# Board.net
KiCad netlist of a schematic drawn in EAGLE
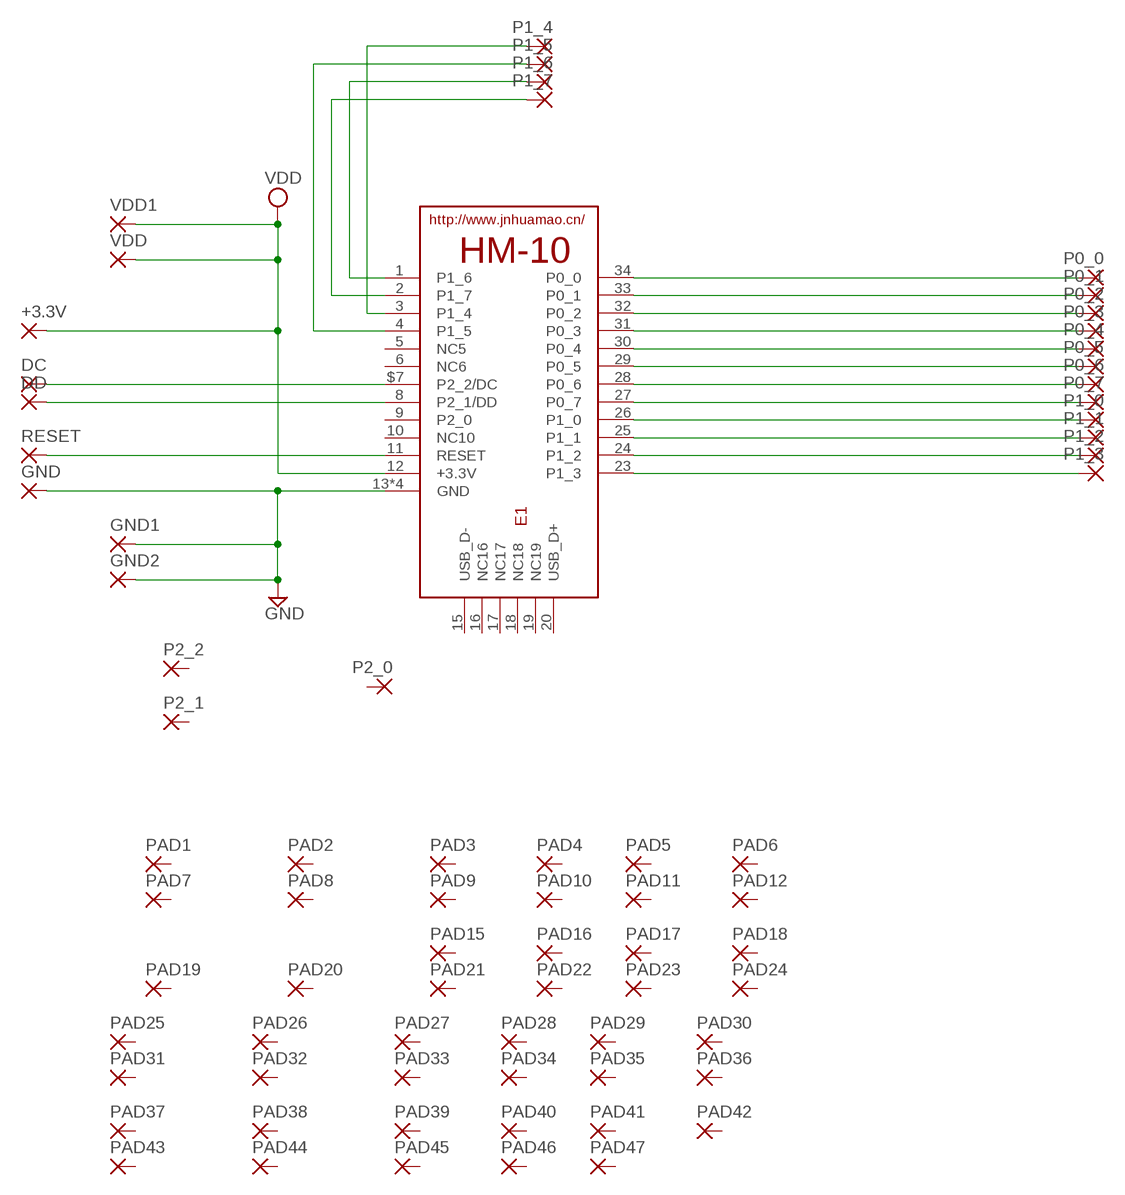
[diagram p0: schematic, sheet 1]

(export (version "E")
  (design (tool "Eeschema 10.0.6"))
  (components
    (comp (ref "+3.3V")
      (value "SMD2")
      (footprint "eagle-import:SMD1,27-2,54")
      (libsource (lib "eagle-import") (part "SMD2"))
    )
    (comp (ref "DC")
      (value "SMD2")
      (footprint "eagle-import:SMD1,27-2,54")
      (libsource (lib "eagle-import") (part "SMD2"))
    )
    (comp (ref "DD")
      (value "SMD2")
      (footprint "eagle-import:SMD1,27-2,54")
      (libsource (lib "eagle-import") (part "SMD2"))
    )
    (comp (ref "E1")
      (value "HM-10-BOARD")
      (footprint "eagle-import:26.9X13X2.2_BOARD")
      (libsource (lib "eagle-import") (part "HM-10-BOARD"))
    )
    (comp (ref "GND")
      (value "SMD2")
      (footprint "eagle-import:SMD1,27-2,54")
      (libsource (lib "eagle-import") (part "SMD2"))
    )
    (comp (ref "GND1")
      (value "1,6/0,9")
      (footprint "eagle-import:1,6_0,9")
      (libsource (lib "eagle-import") (part "1,6/0,9"))
    )
    (comp (ref "GND2")
      (value "1,6/0,9")
      (footprint "eagle-import:1,6_0,9")
      (libsource (lib "eagle-import") (part "1,6/0,9"))
    )
    (comp (ref "P0_0")
      (value "1,6/0,9")
      (footprint "eagle-import:1,6_0,9")
      (libsource (lib "eagle-import") (part "1,6/0,9"))
    )
    (comp (ref "P0_1")
      (value "1,6/0,9")
      (footprint "eagle-import:1,6_0,9")
      (libsource (lib "eagle-import") (part "1,6/0,9"))
    )
    (comp (ref "P0_2")
      (value "1,6/0,9")
      (footprint "eagle-import:1,6_0,9")
      (libsource (lib "eagle-import") (part "1,6/0,9"))
    )
    (comp (ref "P0_3")
      (value "1,6/0,9")
      (footprint "eagle-import:1,6_0,9")
      (libsource (lib "eagle-import") (part "1,6/0,9"))
    )
    (comp (ref "P0_4")
      (value "1,6/0,9")
      (footprint "eagle-import:1,6_0,9")
      (libsource (lib "eagle-import") (part "1,6/0,9"))
    )
    (comp (ref "P0_5")
      (value "1,6/0,9")
      (footprint "eagle-import:1,6_0,9")
      (libsource (lib "eagle-import") (part "1,6/0,9"))
    )
    (comp (ref "P0_6")
      (value "1,6/0,9")
      (footprint "eagle-import:1,6_0,9")
      (libsource (lib "eagle-import") (part "1,6/0,9"))
    )
    (comp (ref "P0_7")
      (value "1,6/0,9")
      (footprint "eagle-import:1,6_0,9")
      (libsource (lib "eagle-import") (part "1,6/0,9"))
    )
    (comp (ref "P1_0")
      (value "1,6/0,9")
      (footprint "eagle-import:1,6_0,9")
      (libsource (lib "eagle-import") (part "1,6/0,9"))
    )
    (comp (ref "P1_1")
      (value "1,6/0,9")
      (footprint "eagle-import:1,6_0,9")
      (libsource (lib "eagle-import") (part "1,6/0,9"))
    )
    (comp (ref "P1_2")
      (value "1,6/0,9")
      (footprint "eagle-import:1,6_0,9")
      (libsource (lib "eagle-import") (part "1,6/0,9"))
    )
    (comp (ref "P1_3")
      (value "1,6/0,9")
      (footprint "eagle-import:1,6_0,9")
      (libsource (lib "eagle-import") (part "1,6/0,9"))
    )
    (comp (ref "P1_4")
      (value "1,6/0,9")
      (footprint "eagle-import:1,6_0,9")
      (libsource (lib "eagle-import") (part "1,6/0,9"))
    )
    (comp (ref "P1_5")
      (value "1,6/0,9")
      (footprint "eagle-import:1,6_0,9")
      (libsource (lib "eagle-import") (part "1,6/0,9"))
    )
    (comp (ref "P1_6")
      (value "1,6/0,9")
      (footprint "eagle-import:1,6_0,9")
      (libsource (lib "eagle-import") (part "1,6/0,9"))
    )
    (comp (ref "P1_7")
      (value "1,6/0,9")
      (footprint "eagle-import:1,6_0,9")
      (libsource (lib "eagle-import") (part "1,6/0,9"))
    )
    (comp (ref "P2_0")
      (value "1,6/0,9")
      (footprint "eagle-import:1,6_0,9")
      (libsource (lib "eagle-import") (part "1,6/0,9"))
    )
    (comp (ref "P2_1")
      (value "1,6/0,9")
      (footprint "eagle-import:1,6_0,9")
      (libsource (lib "eagle-import") (part "1,6/0,9"))
    )
    (comp (ref "P2_2")
      (value "1,6/0,9")
      (footprint "eagle-import:1,6_0,9")
      (libsource (lib "eagle-import") (part "1,6/0,9"))
    )
    (comp (ref "PAD1")
      (value "1,6/0,9")
      (footprint "eagle-import:1,6_0,9")
      (libsource (lib "eagle-import") (part "1,6/0,9"))
    )
    (comp (ref "PAD2")
      (value "1,6/0,9")
      (footprint "eagle-import:1,6_0,9")
      (libsource (lib "eagle-import") (part "1,6/0,9"))
    )
    (comp (ref "PAD3")
      (value "1,6/0,9")
      (footprint "eagle-import:1,6_0,9")
      (libsource (lib "eagle-import") (part "1,6/0,9"))
    )
    (comp (ref "PAD4")
      (value "1,6/0,9")
      (footprint "eagle-import:1,6_0,9")
      (libsource (lib "eagle-import") (part "1,6/0,9"))
    )
    (comp (ref "PAD5")
      (value "1,6/0,9")
      (footprint "eagle-import:1,6_0,9")
      (libsource (lib "eagle-import") (part "1,6/0,9"))
    )
    (comp (ref "PAD6")
      (value "1,6/0,9")
      (footprint "eagle-import:1,6_0,9")
      (libsource (lib "eagle-import") (part "1,6/0,9"))
    )
    (comp (ref "PAD7")
      (value "1,6/0,9")
      (footprint "eagle-import:1,6_0,9")
      (libsource (lib "eagle-import") (part "1,6/0,9"))
    )
    (comp (ref "PAD8")
      (value "1,6/0,9")
      (footprint "eagle-import:1,6_0,9")
      (libsource (lib "eagle-import") (part "1,6/0,9"))
    )
    (comp (ref "PAD9")
      (value "1,6/0,9")
      (footprint "eagle-import:1,6_0,9")
      (libsource (lib "eagle-import") (part "1,6/0,9"))
    )
    (comp (ref "PAD10")
      (value "1,6/0,9")
      (footprint "eagle-import:1,6_0,9")
      (libsource (lib "eagle-import") (part "1,6/0,9"))
    )
    (comp (ref "PAD11")
      (value "1,6/0,9")
      (footprint "eagle-import:1,6_0,9")
      (libsource (lib "eagle-import") (part "1,6/0,9"))
    )
    (comp (ref "PAD12")
      (value "1,6/0,9")
      (footprint "eagle-import:1,6_0,9")
      (libsource (lib "eagle-import") (part "1,6/0,9"))
    )
    (comp (ref "PAD15")
      (value "1,6/0,9")
      (footprint "eagle-import:1,6_0,9")
      (libsource (lib "eagle-import") (part "1,6/0,9"))
    )
    (comp (ref "PAD16")
      (value "1,6/0,9")
      (footprint "eagle-import:1,6_0,9")
      (libsource (lib "eagle-import") (part "1,6/0,9"))
    )
    (comp (ref "PAD17")
      (value "1,6/0,9")
      (footprint "eagle-import:1,6_0,9")
      (libsource (lib "eagle-import") (part "1,6/0,9"))
    )
    (comp (ref "PAD18")
      (value "1,6/0,9")
      (footprint "eagle-import:1,6_0,9")
      (libsource (lib "eagle-import") (part "1,6/0,9"))
    )
    (comp (ref "PAD19")
      (value "1,6/0,9")
      (footprint "eagle-import:1,6_0,9")
      (libsource (lib "eagle-import") (part "1,6/0,9"))
    )
    (comp (ref "PAD20")
      (value "1,6/0,9")
      (footprint "eagle-import:1,6_0,9")
      (libsource (lib "eagle-import") (part "1,6/0,9"))
    )
    (comp (ref "PAD21")
      (value "1,6/0,9")
      (footprint "eagle-import:1,6_0,9")
      (libsource (lib "eagle-import") (part "1,6/0,9"))
    )
    (comp (ref "PAD22")
      (value "1,6/0,9")
      (footprint "eagle-import:1,6_0,9")
      (libsource (lib "eagle-import") (part "1,6/0,9"))
    )
    (comp (ref "PAD23")
      (value "1,6/0,9")
      (footprint "eagle-import:1,6_0,9")
      (libsource (lib "eagle-import") (part "1,6/0,9"))
    )
    (comp (ref "PAD24")
      (value "1,6/0,9")
      (footprint "eagle-import:1,6_0,9")
      (libsource (lib "eagle-import") (part "1,6/0,9"))
    )
    (comp (ref "PAD25")
      (value "1,6/0,9")
      (footprint "eagle-import:1,6_0,9")
      (libsource (lib "eagle-import") (part "1,6/0,9"))
    )
    (comp (ref "PAD26")
      (value "1,6/0,9")
      (footprint "eagle-import:1,6_0,9")
      (libsource (lib "eagle-import") (part "1,6/0,9"))
    )
    (comp (ref "PAD27")
      (value "1,6/0,9")
      (footprint "eagle-import:1,6_0,9")
      (libsource (lib "eagle-import") (part "1,6/0,9"))
    )
    (comp (ref "PAD28")
      (value "1,6/0,9")
      (footprint "eagle-import:1,6_0,9")
      (libsource (lib "eagle-import") (part "1,6/0,9"))
    )
    (comp (ref "PAD29")
      (value "1,6/0,9")
      (footprint "eagle-import:1,6_0,9")
      (libsource (lib "eagle-import") (part "1,6/0,9"))
    )
    (comp (ref "PAD30")
      (value "1,6/0,9")
      (footprint "eagle-import:1,6_0,9")
      (libsource (lib "eagle-import") (part "1,6/0,9"))
    )
    (comp (ref "PAD31")
      (value "1,6/0,9")
      (footprint "eagle-import:1,6_0,9")
      (libsource (lib "eagle-import") (part "1,6/0,9"))
    )
    (comp (ref "PAD32")
      (value "1,6/0,9")
      (footprint "eagle-import:1,6_0,9")
      (libsource (lib "eagle-import") (part "1,6/0,9"))
    )
    (comp (ref "PAD33")
      (value "1,6/0,9")
      (footprint "eagle-import:1,6_0,9")
      (libsource (lib "eagle-import") (part "1,6/0,9"))
    )
    (comp (ref "PAD34")
      (value "1,6/0,9")
      (footprint "eagle-import:1,6_0,9")
      (libsource (lib "eagle-import") (part "1,6/0,9"))
    )
    (comp (ref "PAD35")
      (value "1,6/0,9")
      (footprint "eagle-import:1,6_0,9")
      (libsource (lib "eagle-import") (part "1,6/0,9"))
    )
    (comp (ref "PAD36")
      (value "1,6/0,9")
      (footprint "eagle-import:1,6_0,9")
      (libsource (lib "eagle-import") (part "1,6/0,9"))
    )
    (comp (ref "PAD37")
      (value "1,6/0,9")
      (footprint "eagle-import:1,6_0,9")
      (libsource (lib "eagle-import") (part "1,6/0,9"))
    )
    (comp (ref "PAD38")
      (value "1,6/0,9")
      (footprint "eagle-import:1,6_0,9")
      (libsource (lib "eagle-import") (part "1,6/0,9"))
    )
    (comp (ref "PAD39")
      (value "1,6/0,9")
      (footprint "eagle-import:1,6_0,9")
      (libsource (lib "eagle-import") (part "1,6/0,9"))
    )
    (comp (ref "PAD40")
      (value "1,6/0,9")
      (footprint "eagle-import:1,6_0,9")
      (libsource (lib "eagle-import") (part "1,6/0,9"))
    )
    (comp (ref "PAD41")
      (value "1,6/0,9")
      (footprint "eagle-import:1,6_0,9")
      (libsource (lib "eagle-import") (part "1,6/0,9"))
    )
    (comp (ref "PAD42")
      (value "1,6/0,9")
      (footprint "eagle-import:1,6_0,9")
      (libsource (lib "eagle-import") (part "1,6/0,9"))
    )
    (comp (ref "PAD43")
      (value "1,6/0,9")
      (footprint "eagle-import:1,6_0,9")
      (libsource (lib "eagle-import") (part "1,6/0,9"))
    )
    (comp (ref "PAD44")
      (value "1,6/0,9")
      (footprint "eagle-import:1,6_0,9")
      (libsource (lib "eagle-import") (part "1,6/0,9"))
    )
    (comp (ref "PAD45")
      (value "1,6/0,9")
      (footprint "eagle-import:1,6_0,9")
      (libsource (lib "eagle-import") (part "1,6/0,9"))
    )
    (comp (ref "PAD46")
      (value "1,6/0,9")
      (footprint "eagle-import:1,6_0,9")
      (libsource (lib "eagle-import") (part "1,6/0,9"))
    )
    (comp (ref "PAD47")
      (value "1,6/0,9")
      (footprint "eagle-import:1,6_0,9")
      (libsource (lib "eagle-import") (part "1,6/0,9"))
    )
    (comp (ref "RESET")
      (value "SMD2")
      (footprint "eagle-import:SMD1,27-2,54")
      (libsource (lib "eagle-import") (part "SMD2"))
    )
    (comp (ref "VDD")
      (value "1,6/0,9")
      (footprint "eagle-import:1,6_0,9")
      (libsource (lib "eagle-import") (part "1,6/0,9"))
    )
    (comp (ref "VDD1")
      (value "1,6/0,9")
      (footprint "eagle-import:1,6_0,9")
      (libsource (lib "eagle-import") (part "1,6/0,9"))
    )
  )
  (nets
    (net (code "1") (name "GND") (class "Default")
      (node (ref "E1") (pin "13") (pinfunction "GND_13") (pintype "bidirectional"))
      (node (ref "E1") (pin "14") (pinfunction "GND_14") (pintype "bidirectional"))
      (node (ref "E1") (pin "21") (pinfunction "GND_21") (pintype "bidirectional"))
      (node (ref "E1") (pin "22") (pinfunction "GND_22") (pintype "bidirectional"))
      (node (ref "GND") (pin "1") (pinfunction "P_1") (pintype "passive"))
      (node (ref "GND1") (pin "1") (pinfunction "P_1") (pintype "passive"))
      (node (ref "GND2") (pin "1") (pinfunction "P_1") (pintype "passive"))
    )
    (net (code "2") (name "Net-(DC-P)") (class "Default")
      (node (ref "DC") (pin "1") (pinfunction "P_1") (pintype "passive"))
      (node (ref "E1") (pin "$7") (pinfunction "P2_2/DC_$7") (pintype "bidirectional"))
    )
    (net (code "3") (name "Net-(DD-P)") (class "Default")
      (node (ref "DD") (pin "1") (pinfunction "P_1") (pintype "passive"))
      (node (ref "E1") (pin "8") (pinfunction "P2_1/DD_8") (pintype "bidirectional"))
    )
    (net (code "4") (name "Net-(E1-P0_0)") (class "Default")
      (node (ref "E1") (pin "34") (pinfunction "P0_0_34") (pintype "bidirectional"))
      (node (ref "P0_0") (pin "1") (pinfunction "P_1") (pintype "passive"))
    )
    (net (code "5") (name "Net-(E1-P0_1)") (class "Default")
      (node (ref "E1") (pin "33") (pinfunction "P0_1_33") (pintype "bidirectional"))
      (node (ref "P0_1") (pin "1") (pinfunction "P_1") (pintype "passive"))
    )
    (net (code "6") (name "Net-(E1-P0_2)") (class "Default")
      (node (ref "E1") (pin "32") (pinfunction "P0_2_32") (pintype "bidirectional"))
      (node (ref "P0_2") (pin "1") (pinfunction "P_1") (pintype "passive"))
    )
    (net (code "7") (name "Net-(E1-P0_3)") (class "Default")
      (node (ref "E1") (pin "31") (pinfunction "P0_3_31") (pintype "bidirectional"))
      (node (ref "P0_3") (pin "1") (pinfunction "P_1") (pintype "passive"))
    )
    (net (code "8") (name "Net-(E1-P0_4)") (class "Default")
      (node (ref "E1") (pin "30") (pinfunction "P0_4_30") (pintype "bidirectional"))
      (node (ref "P0_4") (pin "1") (pinfunction "P_1") (pintype "passive"))
    )
    (net (code "9") (name "Net-(E1-P0_5)") (class "Default")
      (node (ref "E1") (pin "29") (pinfunction "P0_5_29") (pintype "bidirectional"))
      (node (ref "P0_5") (pin "1") (pinfunction "P_1") (pintype "passive"))
    )
    (net (code "10") (name "Net-(E1-P0_6)") (class "Default")
      (node (ref "E1") (pin "28") (pinfunction "P0_6_28") (pintype "bidirectional"))
      (node (ref "P0_6") (pin "1") (pinfunction "P_1") (pintype "passive"))
    )
    (net (code "11") (name "Net-(E1-P0_7)") (class "Default")
      (node (ref "E1") (pin "27") (pinfunction "P0_7_27") (pintype "bidirectional"))
      (node (ref "P0_7") (pin "1") (pinfunction "P_1") (pintype "passive"))
    )
    (net (code "12") (name "Net-(E1-P1_0)") (class "Default")
      (node (ref "E1") (pin "26") (pinfunction "P1_0_26") (pintype "bidirectional"))
      (node (ref "P1_0") (pin "1") (pinfunction "P_1") (pintype "passive"))
    )
    (net (code "13") (name "Net-(E1-P1_1)") (class "Default")
      (node (ref "E1") (pin "25") (pinfunction "P1_1_25") (pintype "bidirectional"))
      (node (ref "P1_1") (pin "1") (pinfunction "P_1") (pintype "passive"))
    )
    (net (code "14") (name "Net-(E1-P1_2)") (class "Default")
      (node (ref "E1") (pin "24") (pinfunction "P1_2_24") (pintype "bidirectional"))
      (node (ref "P1_2") (pin "1") (pinfunction "P_1") (pintype "passive"))
    )
    (net (code "15") (name "Net-(E1-P1_3)") (class "Default")
      (node (ref "E1") (pin "23") (pinfunction "P1_3_23") (pintype "bidirectional"))
      (node (ref "P1_3") (pin "1") (pinfunction "P_1") (pintype "passive"))
    )
    (net (code "16") (name "Net-(E1-P1_4)") (class "Default")
      (node (ref "E1") (pin "3") (pinfunction "P1_4_3") (pintype "bidirectional"))
      (node (ref "P1_4") (pin "1") (pinfunction "P_1") (pintype "passive"))
    )
    (net (code "17") (name "Net-(E1-P1_5)") (class "Default")
      (node (ref "E1") (pin "4") (pinfunction "P1_5_4") (pintype "bidirectional"))
      (node (ref "P1_5") (pin "1") (pinfunction "P_1") (pintype "passive"))
    )
    (net (code "18") (name "Net-(E1-P1_6)") (class "Default")
      (node (ref "E1") (pin "1") (pinfunction "P1_6_1") (pintype "bidirectional"))
      (node (ref "P1_6") (pin "1") (pinfunction "P_1") (pintype "passive"))
    )
    (net (code "19") (name "Net-(E1-P1_7)") (class "Default")
      (node (ref "E1") (pin "2") (pinfunction "P1_7_2") (pintype "bidirectional"))
      (node (ref "P1_7") (pin "1") (pinfunction "P_1") (pintype "passive"))
    )
    (net (code "20") (name "Net-(E1-RESET)") (class "Default")
      (node (ref "E1") (pin "11") (pinfunction "RESET_11") (pintype "bidirectional"))
      (node (ref "RESET") (pin "1") (pinfunction "P_1") (pintype "passive"))
    )
    (net (code "21") (name "VDD") (class "Default")
      (node (ref "+3.3V") (pin "1") (pinfunction "P_1") (pintype "passive"))
      (node (ref "E1") (pin "12") (pinfunction "+3.3V_12") (pintype "bidirectional"))
      (node (ref "VDD") (pin "1") (pinfunction "P_1") (pintype "passive"))
      (node (ref "VDD1") (pin "1") (pinfunction "P_1") (pintype "passive"))
    )
    (net (code "22") (name "unconnected-(E1-NC5-Pad5)") (class "Default")
      (node (ref "E1") (pin "5") (pinfunction "NC5_5") (pintype "bidirectional"))
    )
    (net (code "23") (name "unconnected-(E1-NC6-Pad6)") (class "Default")
      (node (ref "E1") (pin "6") (pinfunction "NC6_6") (pintype "bidirectional"))
    )
    (net (code "24") (name "unconnected-(E1-NC10-Pad10)") (class "Default")
      (node (ref "E1") (pin "10") (pinfunction "NC10_10") (pintype "bidirectional"))
    )
    (net (code "25") (name "unconnected-(E1-NC16-Pad16)") (class "Default")
      (node (ref "E1") (pin "16") (pinfunction "NC16_16") (pintype "bidirectional"))
    )
    (net (code "26") (name "unconnected-(E1-NC17-Pad17)") (class "Default")
      (node (ref "E1") (pin "17") (pinfunction "NC17_17") (pintype "bidirectional"))
    )
    (net (code "27") (name "unconnected-(E1-NC18-Pad18)") (class "Default")
      (node (ref "E1") (pin "18") (pinfunction "NC18_18") (pintype "bidirectional"))
    )
    (net (code "28") (name "unconnected-(E1-NC19-Pad19)") (class "Default")
      (node (ref "E1") (pin "19") (pinfunction "NC19_19") (pintype "bidirectional"))
    )
    (net (code "29") (name "unconnected-(E1-P2_0-Pad9)") (class "Default")
      (node (ref "E1") (pin "9") (pinfunction "P2_0_9") (pintype "bidirectional"))
    )
    (net (code "30") (name "unconnected-(E1-USB_D+-Pad20)") (class "Default")
      (node (ref "E1") (pin "20") (pinfunction "USB_D+_20") (pintype "bidirectional"))
    )
    (net (code "31") (name "unconnected-(E1-USB_D--Pad15)") (class "Default")
      (node (ref "E1") (pin "15") (pinfunction "USB_D-_15") (pintype "bidirectional"))
    )
    (net (code "32") (name "unconnected-(P2_0-P-Pad1)") (class "Default")
      (node (ref "P2_0") (pin "1") (pinfunction "P_1") (pintype "passive"))
    )
    (net (code "33") (name "unconnected-(P2_1-P-Pad1)") (class "Default")
      (node (ref "P2_1") (pin "1") (pinfunction "P_1") (pintype "passive"))
    )
    (net (code "34") (name "unconnected-(P2_2-P-Pad1)") (class "Default")
      (node (ref "P2_2") (pin "1") (pinfunction "P_1") (pintype "passive"))
    )
    (net (code "35") (name "unconnected-(PAD1-P-Pad1)") (class "Default")
      (node (ref "PAD1") (pin "1") (pinfunction "P_1") (pintype "passive"))
    )
    (net (code "36") (name "unconnected-(PAD2-P-Pad1)") (class "Default")
      (node (ref "PAD2") (pin "1") (pinfunction "P_1") (pintype "passive"))
    )
    (net (code "37") (name "unconnected-(PAD3-P-Pad1)") (class "Default")
      (node (ref "PAD3") (pin "1") (pinfunction "P_1") (pintype "passive"))
    )
    (net (code "38") (name "unconnected-(PAD4-P-Pad1)") (class "Default")
      (node (ref "PAD4") (pin "1") (pinfunction "P_1") (pintype "passive"))
    )
    (net (code "39") (name "unconnected-(PAD5-P-Pad1)") (class "Default")
      (node (ref "PAD5") (pin "1") (pinfunction "P_1") (pintype "passive"))
    )
    (net (code "40") (name "unconnected-(PAD6-P-Pad1)") (class "Default")
      (node (ref "PAD6") (pin "1") (pinfunction "P_1") (pintype "passive"))
    )
    (net (code "41") (name "unconnected-(PAD7-P-Pad1)") (class "Default")
      (node (ref "PAD7") (pin "1") (pinfunction "P_1") (pintype "passive"))
    )
    (net (code "42") (name "unconnected-(PAD8-P-Pad1)") (class "Default")
      (node (ref "PAD8") (pin "1") (pinfunction "P_1") (pintype "passive"))
    )
    (net (code "43") (name "unconnected-(PAD9-P-Pad1)") (class "Default")
      (node (ref "PAD9") (pin "1") (pinfunction "P_1") (pintype "passive"))
    )
    (net (code "44") (name "unconnected-(PAD10-P-Pad1)") (class "Default")
      (node (ref "PAD10") (pin "1") (pinfunction "P_1") (pintype "passive"))
    )
    (net (code "45") (name "unconnected-(PAD11-P-Pad1)") (class "Default")
      (node (ref "PAD11") (pin "1") (pinfunction "P_1") (pintype "passive"))
    )
    (net (code "46") (name "unconnected-(PAD12-P-Pad1)") (class "Default")
      (node (ref "PAD12") (pin "1") (pinfunction "P_1") (pintype "passive"))
    )
    (net (code "47") (name "unconnected-(PAD15-P-Pad1)") (class "Default")
      (node (ref "PAD15") (pin "1") (pinfunction "P_1") (pintype "passive"))
    )
    (net (code "48") (name "unconnected-(PAD16-P-Pad1)") (class "Default")
      (node (ref "PAD16") (pin "1") (pinfunction "P_1") (pintype "passive"))
    )
    (net (code "49") (name "unconnected-(PAD17-P-Pad1)") (class "Default")
      (node (ref "PAD17") (pin "1") (pinfunction "P_1") (pintype "passive"))
    )
    (net (code "50") (name "unconnected-(PAD18-P-Pad1)") (class "Default")
      (node (ref "PAD18") (pin "1") (pinfunction "P_1") (pintype "passive"))
    )
    (net (code "51") (name "unconnected-(PAD19-P-Pad1)") (class "Default")
      (node (ref "PAD19") (pin "1") (pinfunction "P_1") (pintype "passive"))
    )
    (net (code "52") (name "unconnected-(PAD20-P-Pad1)") (class "Default")
      (node (ref "PAD20") (pin "1") (pinfunction "P_1") (pintype "passive"))
    )
    (net (code "53") (name "unconnected-(PAD21-P-Pad1)") (class "Default")
      (node (ref "PAD21") (pin "1") (pinfunction "P_1") (pintype "passive"))
    )
    (net (code "54") (name "unconnected-(PAD22-P-Pad1)") (class "Default")
      (node (ref "PAD22") (pin "1") (pinfunction "P_1") (pintype "passive"))
    )
    (net (code "55") (name "unconnected-(PAD23-P-Pad1)") (class "Default")
      (node (ref "PAD23") (pin "1") (pinfunction "P_1") (pintype "passive"))
    )
    (net (code "56") (name "unconnected-(PAD24-P-Pad1)") (class "Default")
      (node (ref "PAD24") (pin "1") (pinfunction "P_1") (pintype "passive"))
    )
    (net (code "57") (name "unconnected-(PAD25-P-Pad1)") (class "Default")
      (node (ref "PAD25") (pin "1") (pinfunction "P_1") (pintype "passive"))
    )
    (net (code "58") (name "unconnected-(PAD26-P-Pad1)") (class "Default")
      (node (ref "PAD26") (pin "1") (pinfunction "P_1") (pintype "passive"))
    )
    (net (code "59") (name "unconnected-(PAD27-P-Pad1)") (class "Default")
      (node (ref "PAD27") (pin "1") (pinfunction "P_1") (pintype "passive"))
    )
    (net (code "60") (name "unconnected-(PAD28-P-Pad1)") (class "Default")
      (node (ref "PAD28") (pin "1") (pinfunction "P_1") (pintype "passive"))
    )
    (net (code "61") (name "unconnected-(PAD29-P-Pad1)") (class "Default")
      (node (ref "PAD29") (pin "1") (pinfunction "P_1") (pintype "passive"))
    )
    (net (code "62") (name "unconnected-(PAD30-P-Pad1)") (class "Default")
      (node (ref "PAD30") (pin "1") (pinfunction "P_1") (pintype "passive"))
    )
    (net (code "63") (name "unconnected-(PAD31-P-Pad1)") (class "Default")
      (node (ref "PAD31") (pin "1") (pinfunction "P_1") (pintype "passive"))
    )
    (net (code "64") (name "unconnected-(PAD32-P-Pad1)") (class "Default")
      (node (ref "PAD32") (pin "1") (pinfunction "P_1") (pintype "passive"))
    )
    (net (code "65") (name "unconnected-(PAD33-P-Pad1)") (class "Default")
      (node (ref "PAD33") (pin "1") (pinfunction "P_1") (pintype "passive"))
    )
    (net (code "66") (name "unconnected-(PAD34-P-Pad1)") (class "Default")
      (node (ref "PAD34") (pin "1") (pinfunction "P_1") (pintype "passive"))
    )
    (net (code "67") (name "unconnected-(PAD35-P-Pad1)") (class "Default")
      (node (ref "PAD35") (pin "1") (pinfunction "P_1") (pintype "passive"))
    )
    (net (code "68") (name "unconnected-(PAD36-P-Pad1)") (class "Default")
      (node (ref "PAD36") (pin "1") (pinfunction "P_1") (pintype "passive"))
    )
    (net (code "69") (name "unconnected-(PAD37-P-Pad1)") (class "Default")
      (node (ref "PAD37") (pin "1") (pinfunction "P_1") (pintype "passive"))
    )
    (net (code "70") (name "unconnected-(PAD38-P-Pad1)") (class "Default")
      (node (ref "PAD38") (pin "1") (pinfunction "P_1") (pintype "passive"))
    )
    (net (code "71") (name "unconnected-(PAD39-P-Pad1)") (class "Default")
      (node (ref "PAD39") (pin "1") (pinfunction "P_1") (pintype "passive"))
    )
    (net (code "72") (name "unconnected-(PAD40-P-Pad1)") (class "Default")
      (node (ref "PAD40") (pin "1") (pinfunction "P_1") (pintype "passive"))
    )
    (net (code "73") (name "unconnected-(PAD41-P-Pad1)") (class "Default")
      (node (ref "PAD41") (pin "1") (pinfunction "P_1") (pintype "passive"))
    )
    (net (code "74") (name "unconnected-(PAD42-P-Pad1)") (class "Default")
      (node (ref "PAD42") (pin "1") (pinfunction "P_1") (pintype "passive"))
    )
    (net (code "75") (name "unconnected-(PAD43-P-Pad1)") (class "Default")
      (node (ref "PAD43") (pin "1") (pinfunction "P_1") (pintype "passive"))
    )
    (net (code "76") (name "unconnected-(PAD44-P-Pad1)") (class "Default")
      (node (ref "PAD44") (pin "1") (pinfunction "P_1") (pintype "passive"))
    )
    (net (code "77") (name "unconnected-(PAD45-P-Pad1)") (class "Default")
      (node (ref "PAD45") (pin "1") (pinfunction "P_1") (pintype "passive"))
    )
    (net (code "78") (name "unconnected-(PAD46-P-Pad1)") (class "Default")
      (node (ref "PAD46") (pin "1") (pinfunction "P_1") (pintype "passive"))
    )
    (net (code "79") (name "unconnected-(PAD47-P-Pad1)") (class "Default")
      (node (ref "PAD47") (pin "1") (pinfunction "P_1") (pintype "passive"))
    )
  )
)
